# main.net
KiCad netlist of a schematic drawn in EAGLE
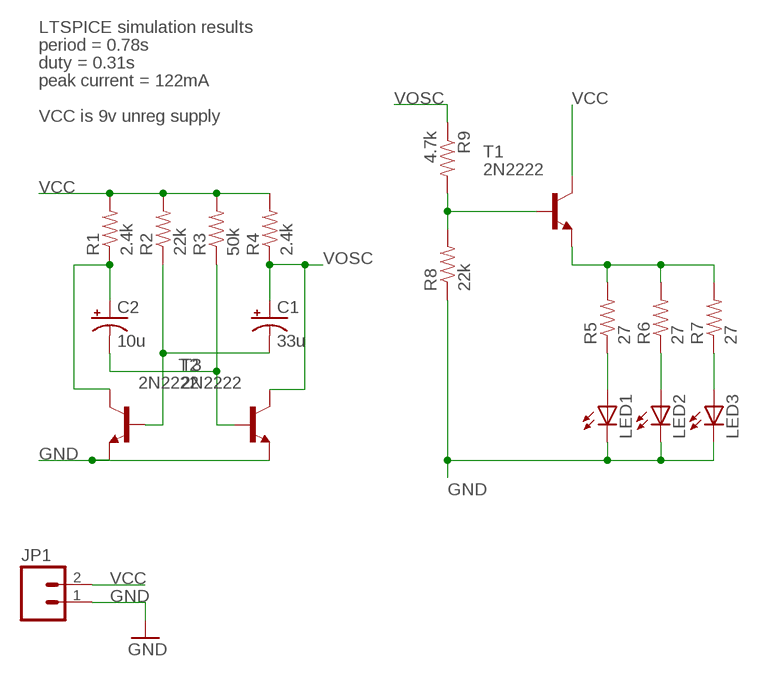
[diagram p0: schematic, sheet 1]

(export (version "E")
  (design (tool "Eeschema 10.0.6"))
  (components
    (comp (ref "C1")
      (value "33u")
      (footprint "eagle-import:CPOL-RADIAL-100UF-25V")
      (libsource (lib "eagle-import") (part "CAP_POLPTH1"))
    )
    (comp (ref "C2")
      (value "10u")
      (footprint "eagle-import:CPOL-RADIAL-100UF-25V")
      (libsource (lib "eagle-import") (part "CAP_POLPTH1"))
    )
    (comp (ref "JP1")
      (value "M02LOCK")
      (footprint "eagle-import:1X02_LOCK")
      (libsource (lib "eagle-import") (part "M02LOCK"))
    )
    (comp (ref "LED1")
      (value "LED5MM")
      (footprint "eagle-import:LED5MM")
      (libsource (lib "eagle-import") (part "LED5MM"))
    )
    (comp (ref "LED2")
      (value "LED5MM")
      (footprint "eagle-import:LED5MM")
      (libsource (lib "eagle-import") (part "LED5MM"))
    )
    (comp (ref "LED3")
      (value "LED5MM")
      (footprint "eagle-import:LED5MM")
      (libsource (lib "eagle-import") (part "LED5MM"))
    )
    (comp (ref "R1")
      (value "2.4k")
      (footprint "eagle-import:AXIAL-0.4")
      (libsource (lib "eagle-import") (part "RESISTORPTH-1/4W"))
    )
    (comp (ref "R2")
      (value "22k")
      (footprint "eagle-import:AXIAL-0.4")
      (libsource (lib "eagle-import") (part "RESISTORPTH-1/4W"))
    )
    (comp (ref "R3")
      (value "50k")
      (footprint "eagle-import:AXIAL-0.4")
      (libsource (lib "eagle-import") (part "RESISTORPTH-1/4W"))
    )
    (comp (ref "R4")
      (value "2.4k")
      (footprint "eagle-import:AXIAL-0.4")
      (libsource (lib "eagle-import") (part "RESISTORPTH-1/4W"))
    )
    (comp (ref "R5")
      (value "27")
      (footprint "eagle-import:AXIAL-0.4")
      (libsource (lib "eagle-import") (part "RESISTORPTH-1/4W"))
    )
    (comp (ref "R6")
      (value "27")
      (footprint "eagle-import:AXIAL-0.4")
      (libsource (lib "eagle-import") (part "RESISTORPTH-1/4W"))
    )
    (comp (ref "R7")
      (value "27")
      (footprint "eagle-import:AXIAL-0.4")
      (libsource (lib "eagle-import") (part "RESISTORPTH-1/4W"))
    )
    (comp (ref "R8")
      (value "22k")
      (footprint "eagle-import:AXIAL-0.4")
      (libsource (lib "eagle-import") (part "RESISTORPTH-1/4W"))
    )
    (comp (ref "R9")
      (value "4.7k")
      (footprint "eagle-import:AXIAL-0.4")
      (libsource (lib "eagle-import") (part "RESISTORPTH-1/4W"))
    )
    (comp (ref "T1")
      (value "2N2222")
      (footprint "eagle-import:TO18")
      (libsource (lib "eagle-import") (part "2N2222"))
    )
    (comp (ref "T2")
      (value "2N2222")
      (footprint "eagle-import:TO18")
      (libsource (lib "eagle-import") (part "2N2222"))
    )
    (comp (ref "T3")
      (value "2N2222")
      (footprint "eagle-import:TO18")
      (libsource (lib "eagle-import") (part "2N2222"))
    )
  )
  (nets
    (net (code "1") (name "/VCC") (class "Default")
      (node (ref "JP1") (pin "2") (pinfunction "2_2") (pintype "passive"))
      (node (ref "R1") (pin "P$2") (pinfunction "2_P$2") (pintype "passive"))
      (node (ref "R2") (pin "P$2") (pinfunction "2_P$2") (pintype "passive"))
      (node (ref "R3") (pin "P$2") (pinfunction "2_P$2") (pintype "passive"))
      (node (ref "R4") (pin "P$2") (pinfunction "2_P$2") (pintype "passive"))
      (node (ref "T1") (pin "3") (pinfunction "C_3") (pintype "passive"))
    )
    (net (code "2") (name "/VOSC") (class "Default")
      (node (ref "C1") (pin "1") (pinfunction "+_1") (pintype "passive"))
      (node (ref "R4") (pin "P$1") (pinfunction "1_P$1") (pintype "passive"))
      (node (ref "R9") (pin "P$1") (pinfunction "1_P$1") (pintype "passive"))
      (node (ref "T3") (pin "3") (pinfunction "C_3") (pintype "passive"))
    )
    (net (code "3") (name "GND") (class "Default")
      (node (ref "JP1") (pin "1") (pinfunction "1_1") (pintype "passive"))
      (node (ref "LED1") (pin "K") (pinfunction "C_K") (pintype "passive"))
      (node (ref "LED2") (pin "K") (pinfunction "C_K") (pintype "passive"))
      (node (ref "LED3") (pin "K") (pinfunction "C_K") (pintype "passive"))
      (node (ref "R8") (pin "P$1") (pinfunction "1_P$1") (pintype "passive"))
      (node (ref "T2") (pin "1") (pinfunction "E_1") (pintype "passive"))
      (node (ref "T3") (pin "1") (pinfunction "E_1") (pintype "passive"))
    )
    (net (code "4") (name "Net-(C1--)") (class "Default")
      (node (ref "C1") (pin "2") (pinfunction "-_2") (pintype "passive"))
      (node (ref "R2") (pin "P$1") (pinfunction "1_P$1") (pintype "passive"))
      (node (ref "T2") (pin "2") (pinfunction "B_2") (pintype "passive"))
    )
    (net (code "5") (name "Net-(C2-+)") (class "Default")
      (node (ref "C2") (pin "1") (pinfunction "+_1") (pintype "passive"))
      (node (ref "R1") (pin "P$1") (pinfunction "1_P$1") (pintype "passive"))
      (node (ref "T2") (pin "3") (pinfunction "C_3") (pintype "passive"))
    )
    (net (code "6") (name "Net-(C2--)") (class "Default")
      (node (ref "C2") (pin "2") (pinfunction "-_2") (pintype "passive"))
      (node (ref "R3") (pin "P$1") (pinfunction "1_P$1") (pintype "passive"))
      (node (ref "T3") (pin "2") (pinfunction "B_2") (pintype "passive"))
    )
    (net (code "7") (name "Net-(R5-1)") (class "Default")
      (node (ref "LED1") (pin "A") (pinfunction "A_A") (pintype "passive"))
      (node (ref "R5") (pin "P$1") (pinfunction "1_P$1") (pintype "passive"))
    )
    (net (code "8") (name "Net-(R5-2)") (class "Default")
      (node (ref "R5") (pin "P$2") (pinfunction "2_P$2") (pintype "passive"))
      (node (ref "R6") (pin "P$2") (pinfunction "2_P$2") (pintype "passive"))
      (node (ref "R7") (pin "P$2") (pinfunction "2_P$2") (pintype "passive"))
      (node (ref "T1") (pin "1") (pinfunction "E_1") (pintype "passive"))
    )
    (net (code "9") (name "Net-(R6-1)") (class "Default")
      (node (ref "LED2") (pin "A") (pinfunction "A_A") (pintype "passive"))
      (node (ref "R6") (pin "P$1") (pinfunction "1_P$1") (pintype "passive"))
    )
    (net (code "10") (name "Net-(R7-1)") (class "Default")
      (node (ref "LED3") (pin "A") (pinfunction "A_A") (pintype "passive"))
      (node (ref "R7") (pin "P$1") (pinfunction "1_P$1") (pintype "passive"))
    )
    (net (code "11") (name "Net-(R8-2)") (class "Default")
      (node (ref "R8") (pin "P$2") (pinfunction "2_P$2") (pintype "passive"))
      (node (ref "R9") (pin "P$2") (pinfunction "2_P$2") (pintype "passive"))
      (node (ref "T1") (pin "2") (pinfunction "B_2") (pintype "passive"))
    )
  )
)
